# Grove_-_Collision_Sensor_V0_9b.net
KiCad netlist of a schematic drawn in EAGLE
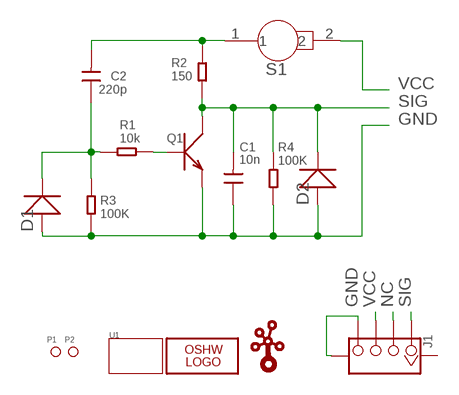
[diagram p0: schematic, sheet 1]

(export (version "E")
  (design (tool "Eeschema 10.0.6"))
  (components
    (comp (ref "C1")
      (value "10n")
      (footprint "eagle-import:0603")
      (libsource (lib "eagle-import") (part "C-0603"))
    )
    (comp (ref "C2")
      (value "220p")
      (footprint "eagle-import:0603")
      (libsource (lib "eagle-import") (part "C-0603"))
    )
    (comp (ref "D1")
      (value "D1N4148-SMD")
      (footprint "eagle-import:DO-35-SMD")
      (libsource (lib "eagle-import") (part "D1N4148-SMD"))
    )
    (comp (ref "D2")
      (value "D1N4148-SMD")
      (footprint "eagle-import:DO-35-SMD")
      (libsource (lib "eagle-import") (part "D1N4148-SMD"))
    )
    (comp (ref "J1")
      (value "TWIG-4P-2.0-SMD-FEMALE-REINFORCE'DD'")
      (footprint "eagle-import:4P-SMD-2.0")
      (libsource (lib "eagle-import") (part "TWIG-4P-2.0-SMD-FEMALE-REINFORCE'DD'"))
    )
    (comp (ref "LOGO1")
      (value "LOGO-OSHW-6MILX0200-NT")
      (footprint "eagle-import:OSHW_6X200_NOTEXT")
      (libsource (lib "eagle-import") (part "LOGO-OSHW-6MILX0200-NT"))
    )
    (comp (ref "P1")
      (value "PAD-MARK")
      (footprint "eagle-import:ROUND-MARK-0.635")
      (libsource (lib "eagle-import") (part "PAD-MARK"))
    )
    (comp (ref "P2")
      (value "PAD-MARK")
      (footprint "eagle-import:ROUND-MARK-0.635")
      (libsource (lib "eagle-import") (part "PAD-MARK"))
    )
    (comp (ref "Q1")
      (value "TRANSISTOR-NPN-SOT23''")
      (footprint "eagle-import:SOT23")
      (libsource (lib "eagle-import") (part "TRANSISTOR-NPN-SOT23''"))
    )
    (comp (ref "R1")
      (value "10k")
      (footprint "eagle-import:0603")
      (libsource (lib "eagle-import") (part "R-0603"))
    )
    (comp (ref "R2")
      (value "150")
      (footprint "eagle-import:0603")
      (libsource (lib "eagle-import") (part "R-0603"))
    )
    (comp (ref "R3")
      (value "100K")
      (footprint "eagle-import:0603")
      (libsource (lib "eagle-import") (part "R-0603"))
    )
    (comp (ref "R4")
      (value "100K")
      (footprint "eagle-import:0603")
      (libsource (lib "eagle-import") (part "R-0603"))
    )
    (comp (ref "S1")
      (value "SENSOR-COLLISION")
      (footprint "eagle-import:2P-ROUND-D5.4MM")
      (libsource (lib "eagle-import") (part "SENSOR-COLLISION"))
    )
    (comp (ref "U$2")
      (value "LOGO-TWIG")
      (footprint "eagle-import:TWIGLOGO")
      (libsource (lib "eagle-import") (part "LOGO-TWIG"))
    )
    (comp (ref "U1")
      (value "TWIG-1U")
      (footprint "eagle-import:1U-DIM-W_-DRILL")
      (libsource (lib "eagle-import") (part "TWIG-1U"))
    )
  )
  (nets
    (net (code "1") (name "/GND") (class "Default")
      (node (ref "C1") (pin "1") (pinfunction "1_1") (pintype "passive"))
      (node (ref "D1") (pin "A") (pinfunction "+_A") (pintype "passive"))
      (node (ref "D2") (pin "A") (pinfunction "+_A") (pintype "passive"))
      (node (ref "J1") (pin "4") (pinfunction "4_4") (pintype "bidirectional"))
      (node (ref "J1") (pin "SS2") (pinfunction "SS2_SS2") (pintype "bidirectional"))
      (node (ref "Q1") (pin "2") (pinfunction "E_2") (pintype "passive"))
      (node (ref "R3") (pin "2") (pinfunction "2_2") (pintype "passive"))
      (node (ref "R4") (pin "2") (pinfunction "2_2") (pintype "passive"))
    )
    (net (code "2") (name "/NC") (class "Default")
      (node (ref "J1") (pin "2") (pinfunction "2_2") (pintype "bidirectional"))
    )
    (net (code "3") (name "/SIG") (class "Default")
      (node (ref "C1") (pin "2") (pinfunction "2_2") (pintype "passive"))
      (node (ref "D2") (pin "C") (pinfunction "-_C") (pintype "passive"))
      (node (ref "J1") (pin "1") (pinfunction "1_1") (pintype "bidirectional"))
      (node (ref "Q1") (pin "3") (pinfunction "C_3") (pintype "passive"))
      (node (ref "R2") (pin "2") (pinfunction "2_2") (pintype "passive"))
      (node (ref "R4") (pin "1") (pinfunction "1_1") (pintype "passive"))
    )
    (net (code "4") (name "/VCC") (class "Default")
      (node (ref "J1") (pin "3") (pinfunction "3_3") (pintype "bidirectional"))
      (node (ref "S1") (pin "2") (pinfunction "2_2") (pintype "bidirectional"))
    )
    (net (code "5") (name "Net-(C2-Pad2)") (class "Default")
      (node (ref "C2") (pin "2") (pinfunction "2_2") (pintype "passive"))
      (node (ref "R2") (pin "1") (pinfunction "1_1") (pintype "passive"))
      (node (ref "S1") (pin "1") (pinfunction "1_1") (pintype "bidirectional"))
    )
    (net (code "6") (name "Net-(D1--)") (class "Default")
      (node (ref "C2") (pin "1") (pinfunction "1_1") (pintype "passive"))
      (node (ref "D1") (pin "C") (pinfunction "-_C") (pintype "passive"))
      (node (ref "R1") (pin "2") (pinfunction "2_2") (pintype "passive"))
      (node (ref "R3") (pin "1") (pinfunction "1_1") (pintype "passive"))
    )
    (net (code "7") (name "Net-(Q1-B)") (class "Default")
      (node (ref "Q1") (pin "1") (pinfunction "B_1") (pintype "passive"))
      (node (ref "R1") (pin "1") (pinfunction "1_1") (pintype "passive"))
    )
    (net (code "8") (name "unconnected-(J1-PadSS1)") (class "Default")
      (node (ref "J1") (pin "SS1") (pinfunction "SS1_SS1") (pintype "bidirectional"))
    )
  )
)
